# DB10011_Converter.net
KiCad netlist of a schematic drawn in Altium Designer
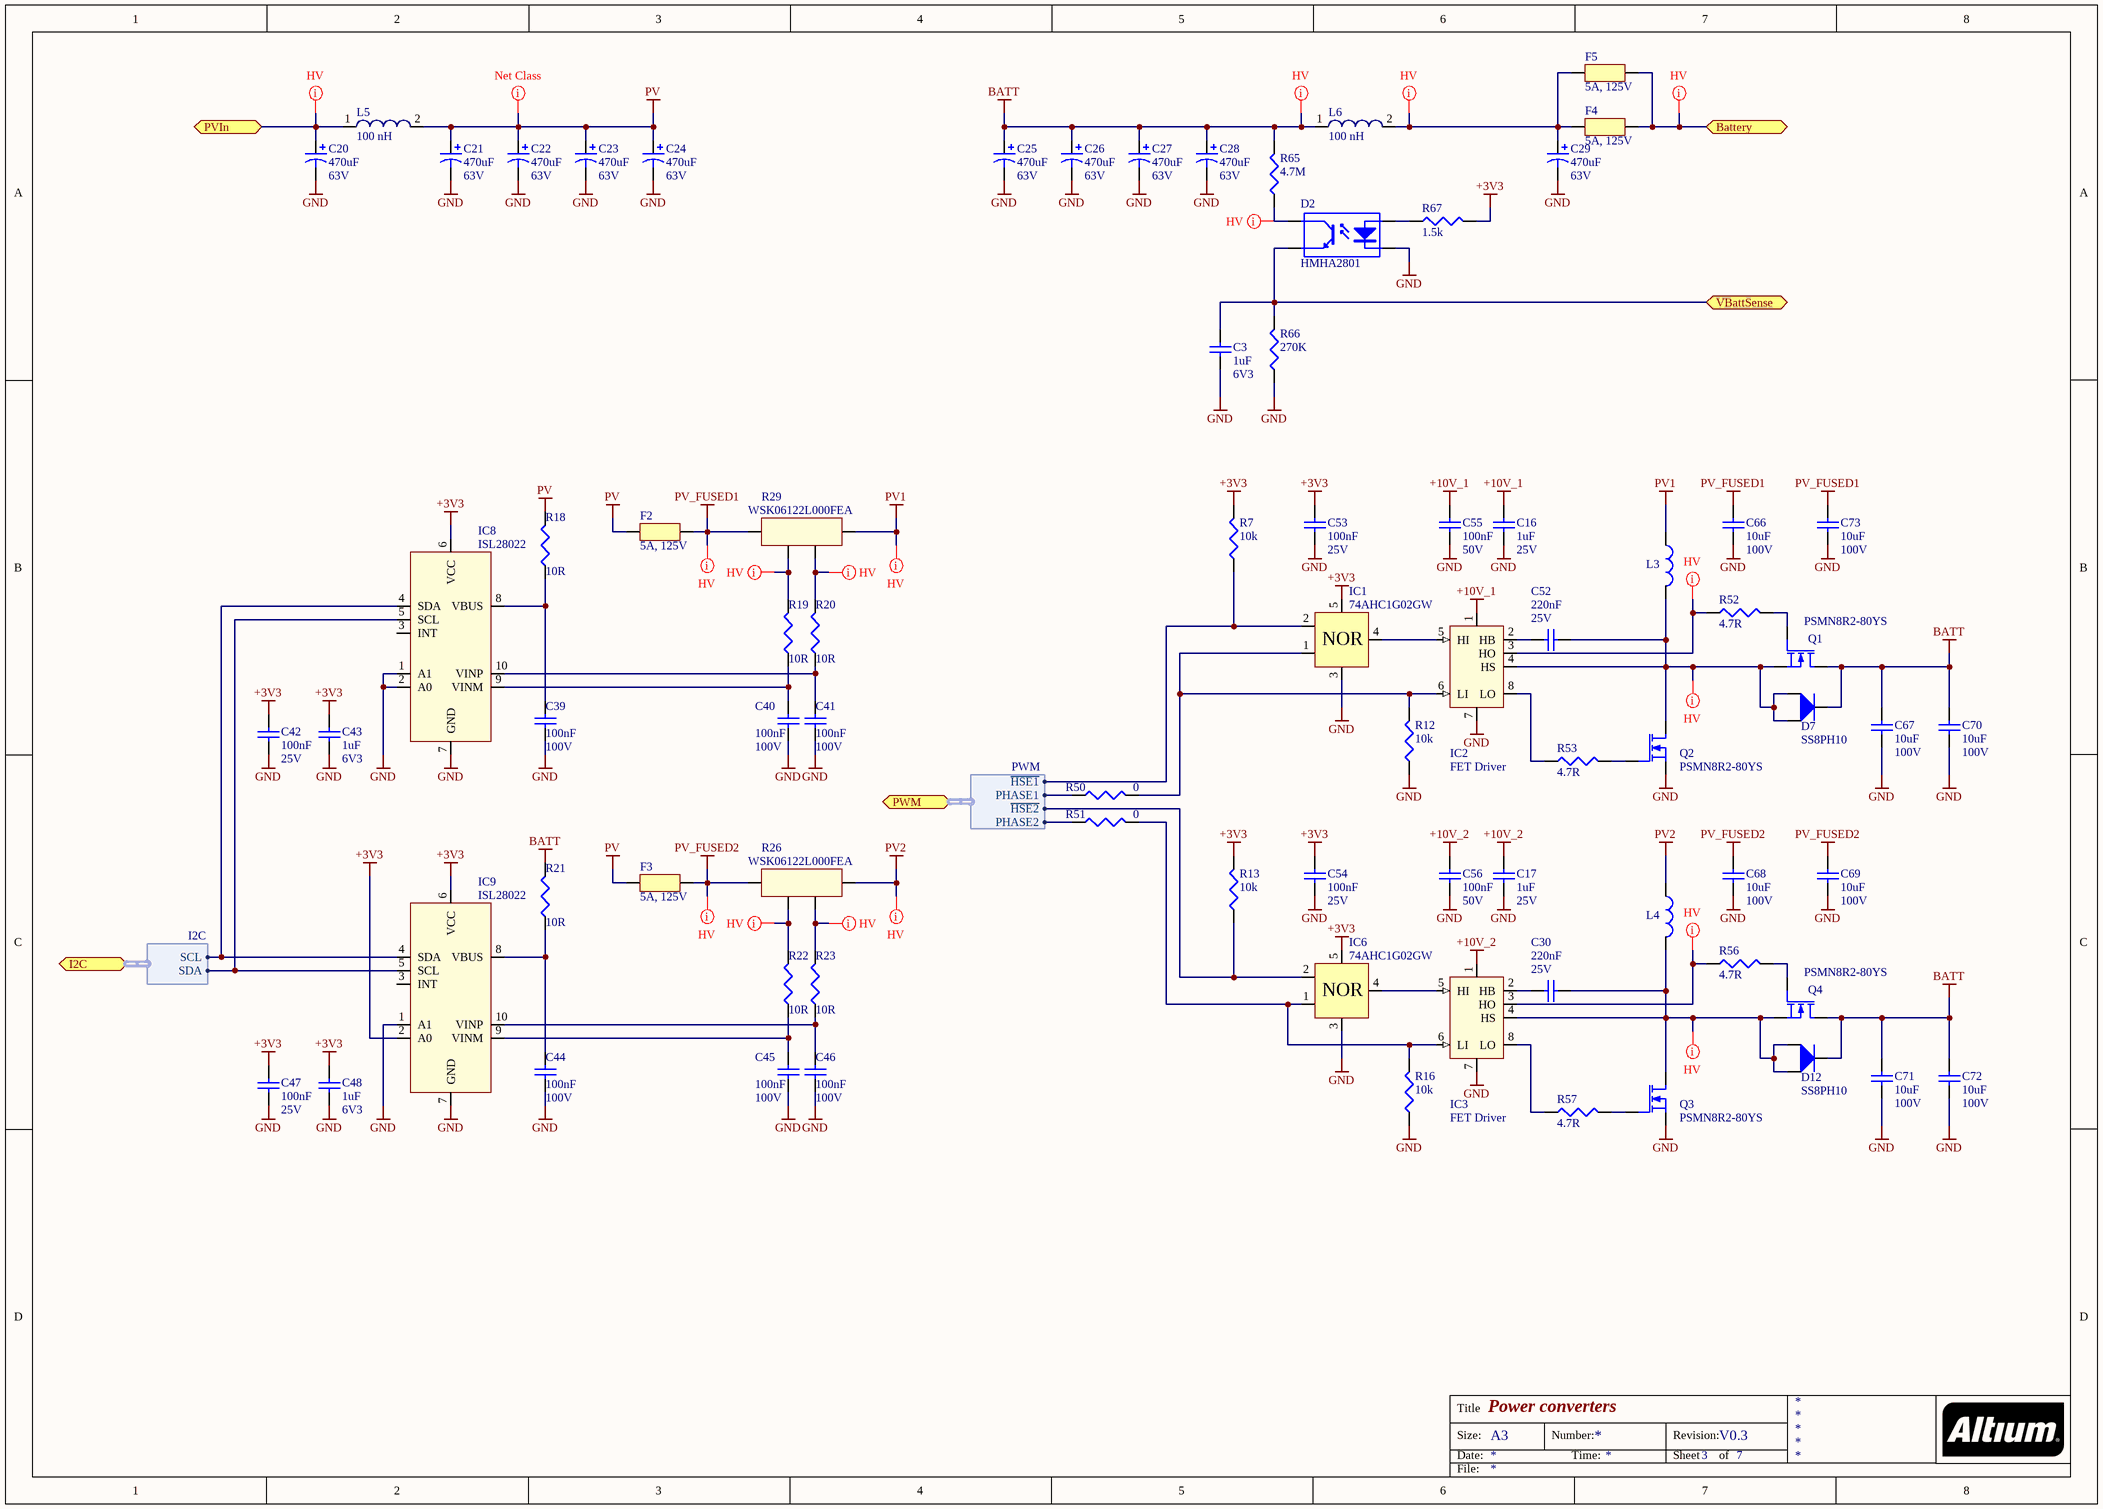
[diagram p0: DB10011_Converter.SchDoc]

(export (version "E")
  (design (tool "Eeschema 10.0.6"))
  (components
    (comp (ref "C3")
      (value "1uF")
      (footprint "C0402")
      (description "Capacitor, 1uF, 6.3V, X5R")
      (fields (field (name "VOLTAGE RATING") "6V3"))
      (libsource (lib "AR_Capacitors_Ceramic") (part "1uF/0402/CER/6.3V"))
    )
    (comp (ref "C16")
      (value "1uF")
      (footprint "C0603")
      (description "Capacitor, 1uF, 25V, X7R")
      (fields (field (name "VOLTAGE RATING") "25V"))
      (libsource (lib "AR_Capacitors_Ceramic") (part "1uF/0603/CER/25V"))
    )
    (comp (ref "C17")
      (value "1uF")
      (footprint "C0603")
      (description "Capacitor, 1uF, 25V, X7R")
      (fields (field (name "VOLTAGE RATING") "25V"))
      (libsource (lib "AR_Capacitors_Ceramic") (part "1uF/0603/CER/25V"))
    )
    (comp (ref "C20")
      (value "470uF")
      (footprint "Radial-16")
      (description "Aluminum Electrolytic Capacitor, 470uF, 63V")
      (fields (field (name "VOLTAGE RATING") "63V"))
      (libsource (lib "AR_Capacitors_Aluminium") (part "470uF/ALU/63V"))
    )
    (comp (ref "C21")
      (value "470uF")
      (footprint "Radial-16")
      (description "Aluminum Electrolytic Capacitor, 470uF, 63V")
      (fields (field (name "VOLTAGE RATING") "63V"))
      (libsource (lib "AR_Capacitors_Aluminium") (part "470uF/ALU/63V"))
    )
    (comp (ref "C22")
      (value "470uF")
      (footprint "Radial-16")
      (description "Aluminum Electrolytic Capacitor, 470uF, 63V")
      (fields (field (name "VOLTAGE RATING") "63V"))
      (libsource (lib "AR_Capacitors_Aluminium") (part "470uF/ALU/63V"))
    )
    (comp (ref "C23")
      (value "470uF")
      (footprint "Radial-16")
      (description "Aluminum Electrolytic Capacitor, 470uF, 63V")
      (fields (field (name "VOLTAGE RATING") "63V"))
      (libsource (lib "AR_Capacitors_Aluminium") (part "470uF/ALU/63V"))
    )
    (comp (ref "C24")
      (value "470uF")
      (footprint "Radial-16")
      (description "Aluminum Electrolytic Capacitor, 470uF, 63V")
      (fields (field (name "VOLTAGE RATING") "63V"))
      (libsource (lib "AR_Capacitors_Aluminium") (part "470uF/ALU/63V"))
    )
    (comp (ref "C25")
      (value "470uF")
      (footprint "Radial-16")
      (description "Aluminum Electrolytic Capacitor, 470uF, 63V")
      (fields (field (name "VOLTAGE RATING") "63V"))
      (libsource (lib "AR_Capacitors_Aluminium") (part "470uF/ALU/63V"))
    )
    (comp (ref "C26")
      (value "470uF")
      (footprint "Radial-16")
      (description "Aluminum Electrolytic Capacitor, 470uF, 63V")
      (fields (field (name "VOLTAGE RATING") "63V"))
      (libsource (lib "AR_Capacitors_Aluminium") (part "470uF/ALU/63V"))
    )
    (comp (ref "C27")
      (value "470uF")
      (footprint "Radial-16")
      (description "Aluminum Electrolytic Capacitor, 470uF, 63V")
      (fields (field (name "VOLTAGE RATING") "63V"))
      (libsource (lib "AR_Capacitors_Aluminium") (part "470uF/ALU/63V"))
    )
    (comp (ref "C28")
      (value "470uF")
      (footprint "Radial-16")
      (description "Aluminum Electrolytic Capacitor, 470uF, 63V")
      (fields (field (name "VOLTAGE RATING") "63V"))
      (libsource (lib "AR_Capacitors_Aluminium") (part "470uF/ALU/63V"))
    )
    (comp (ref "C29")
      (value "470uF")
      (footprint "Radial-16")
      (description "Aluminum Electrolytic Capacitor, 470uF, 63V")
      (fields (field (name "VOLTAGE RATING") "63V"))
      (libsource (lib "AR_Capacitors_Aluminium") (part "470uF/ALU/63V"))
    )
    (comp (ref "C30")
      (value "220nF")
      (footprint "C0603")
      (description "Capacitor, 220nF, 25V, X7R")
      (fields (field (name "VOLTAGE RATING") "25V"))
      (libsource (lib "AR_Capacitors_Ceramic") (part "220nF/0603/CER/25V"))
    )
    (comp (ref "C39")
      (value "100nF")
      (footprint "C-0805")
      (description "Capacitor, 100nF, 100V, X7R")
      (fields (field (name "VOLTAGE RATING") "100V"))
      (libsource (lib "AR_Capacitors_Ceramic") (part "100nF/0805/CER/100V"))
    )
    (comp (ref "C40")
      (value "100nF")
      (footprint "C-0805")
      (description "Capacitor, 100nF, 100V, X7R")
      (fields (field (name "VOLTAGE RATING") "100V"))
      (libsource (lib "AR_Capacitors_Ceramic") (part "100nF/0805/CER/100V"))
    )
    (comp (ref "C41")
      (value "100nF")
      (footprint "C-0805")
      (description "Capacitor, 100nF, 100V, X7R")
      (fields (field (name "VOLTAGE RATING") "100V"))
      (libsource (lib "AR_Capacitors_Ceramic") (part "100nF/0805/CER/100V"))
    )
    (comp (ref "C42")
      (value "100nF")
      (footprint "C0402")
      (description "Capacitor, 100nF, 25V, X7R")
      (fields (field (name "VOLTAGE RATING") "25V"))
      (libsource (lib "AR_Capacitors_Ceramic") (part "100nF/0402/CER/25V"))
    )
    (comp (ref "C43")
      (value "1uF")
      (footprint "C0402")
      (description "Capacitor, 1uF, 6.3V, X5R")
      (fields (field (name "VOLTAGE RATING") "6V3"))
      (libsource (lib "AR_Capacitors_Ceramic") (part "1uF/0402/CER/6.3V"))
    )
    (comp (ref "C44")
      (value "100nF")
      (footprint "C-0805")
      (description "Capacitor, 100nF, 100V, X7R")
      (fields (field (name "VOLTAGE RATING") "100V"))
      (libsource (lib "AR_Capacitors_Ceramic") (part "100nF/0805/CER/100V"))
    )
    (comp (ref "C45")
      (value "100nF")
      (footprint "C-0805")
      (description "Capacitor, 100nF, 100V, X7R")
      (fields (field (name "VOLTAGE RATING") "100V"))
      (libsource (lib "AR_Capacitors_Ceramic") (part "100nF/0805/CER/100V"))
    )
    (comp (ref "C46")
      (value "100nF")
      (footprint "C-0805")
      (description "Capacitor, 100nF, 100V, X7R")
      (fields (field (name "VOLTAGE RATING") "100V"))
      (libsource (lib "AR_Capacitors_Ceramic") (part "100nF/0805/CER/100V"))
    )
    (comp (ref "C47")
      (value "100nF")
      (footprint "C0402")
      (description "Capacitor, 100nF, 25V, X7R")
      (fields (field (name "VOLTAGE RATING") "25V"))
      (libsource (lib "AR_Capacitors_Ceramic") (part "100nF/0402/CER/25V"))
    )
    (comp (ref "C48")
      (value "1uF")
      (footprint "C0402")
      (description "Capacitor, 1uF, 6.3V, X5R")
      (fields (field (name "VOLTAGE RATING") "6V3"))
      (libsource (lib "AR_Capacitors_Ceramic") (part "1uF/0402/CER/6.3V"))
    )
    (comp (ref "C52")
      (value "220nF")
      (footprint "C0603")
      (description "Capacitor, 220nF, 25V, X7R")
      (fields (field (name "VOLTAGE RATING") "25V"))
      (libsource (lib "AR_Capacitors_Ceramic") (part "220nF/0603/CER/25V"))
    )
    (comp (ref "C53")
      (value "100nF")
      (footprint "C0402")
      (description "Capacitor, 100nF, 25V, X7R")
      (fields (field (name "VOLTAGE RATING") "25V"))
      (libsource (lib "AR_Capacitors_Ceramic") (part "100nF/0402/CER/25V"))
    )
    (comp (ref "C54")
      (value "100nF")
      (footprint "C0402")
      (description "Capacitor, 100nF, 25V, X7R")
      (fields (field (name "VOLTAGE RATING") "25V"))
      (libsource (lib "AR_Capacitors_Ceramic") (part "100nF/0402/CER/25V"))
    )
    (comp (ref "C55")
      (value "100nF")
      (footprint "C0603")
      (description "Capacitor, 100nF, 50V, X7R")
      (fields (field (name "VOLTAGE RATING") "50V"))
      (libsource (lib "AR_Capacitors_Ceramic") (part "100nF/0603/CER/50V"))
    )
    (comp (ref "C56")
      (value "100nF")
      (footprint "C0603")
      (description "Capacitor, 100nF, 50V, X7R")
      (fields (field (name "VOLTAGE RATING") "50V"))
      (libsource (lib "AR_Capacitors_Ceramic") (part "100nF/0603/CER/50V"))
    )
    (comp (ref "C66")
      (value "10uF")
      (footprint "C2220")
      (description "Capacitor, 10uF, 100V, X7S")
      (fields (field (name "VOLTAGE RATING") "100V"))
      (libsource (lib "AR_Capacitors_Ceramic") (part "10uF/2220/CER/100V"))
    )
    (comp (ref "C67")
      (value "10uF")
      (footprint "C2220")
      (description "Capacitor, 10uF, 100V, X7S")
      (fields (field (name "VOLTAGE RATING") "100V"))
      (libsource (lib "AR_Capacitors_Ceramic") (part "10uF/2220/CER/100V"))
    )
    (comp (ref "C68")
      (value "10uF")
      (footprint "C2220")
      (description "Capacitor, 10uF, 100V, X7S")
      (fields (field (name "VOLTAGE RATING") "100V"))
      (libsource (lib "AR_Capacitors_Ceramic") (part "10uF/2220/CER/100V"))
    )
    (comp (ref "C69")
      (value "10uF")
      (footprint "C2220")
      (description "Capacitor, 10uF, 100V, X7S")
      (fields (field (name "VOLTAGE RATING") "100V"))
      (libsource (lib "AR_Capacitors_Ceramic") (part "10uF/2220/CER/100V"))
    )
    (comp (ref "C70")
      (value "10uF")
      (footprint "C2220")
      (description "Capacitor, 10uF, 100V, X7S")
      (fields (field (name "VOLTAGE RATING") "100V"))
      (libsource (lib "AR_Capacitors_Ceramic") (part "10uF/2220/CER/100V"))
    )
    (comp (ref "C71")
      (value "10uF")
      (footprint "C2220")
      (description "Capacitor, 10uF, 100V, X7S")
      (fields (field (name "VOLTAGE RATING") "100V"))
      (libsource (lib "AR_Capacitors_Ceramic") (part "10uF/2220/CER/100V"))
    )
    (comp (ref "C72")
      (value "10uF")
      (footprint "C2220")
      (description "Capacitor, 10uF, 100V, X7S")
      (fields (field (name "VOLTAGE RATING") "100V"))
      (libsource (lib "AR_Capacitors_Ceramic") (part "10uF/2220/CER/100V"))
    )
    (comp (ref "C73")
      (value "10uF")
      (footprint "C2220")
      (description "Capacitor, 10uF, 100V, X7S")
      (fields (field (name "VOLTAGE RATING") "100V"))
      (libsource (lib "AR_Capacitors_Ceramic") (part "10uF/2220/CER/100V"))
    )
    (comp (ref "D2")
      (value "HMHA2801")
      (footprint "FSOP4")
      (description "Optocoupler, Vout:80V, Iin:0.01A")
      (libsource (lib "AR_Optocouplers") (part "HMHA2801"))
    )
    (comp (ref "D7")
      (value "SS8PH10")
      (footprint "TO277A")
      (description "Diode 8A 100V")
      (libsource (lib "DannyLib") (part "SS8PH10"))
    )
    (comp (ref "D12")
      (value "SS8PH10")
      (footprint "TO277A")
      (description "Diode 8A 100V")
      (libsource (lib "DannyLib") (part "SS8PH10"))
    )
    (comp (ref "F2")
      (value "5A, 125V")
      (footprint "SMF")
      (description "Fuse, Slow Blow, 5A, 125V, T:-55°C +125°C")
      (libsource (lib "AR_Misc") (part "0452005.MRL"))
    )
    (comp (ref "F3")
      (value "5A, 125V")
      (footprint "SMF")
      (description "Fuse, Slow Blow, 5A, 125V, T:-55°C +125°C")
      (libsource (lib "AR_Misc") (part "0452005.MRL"))
    )
    (comp (ref "F4")
      (value "5A, 125V")
      (footprint "SMF")
      (description "Fuse, Slow Blow, 5A, 125V, T:-55°C +125°C")
      (libsource (lib "AR_Misc") (part "0452005.MRL"))
    )
    (comp (ref "F5")
      (value "5A, 125V")
      (footprint "SMF")
      (description "Fuse, Slow Blow, 5A, 125V, T:-55°C +125°C")
      (libsource (lib "AR_Misc") (part "0452005.MRL"))
    )
    (comp (ref "IC1")
      (value "74AHC1G02GW")
      (footprint "SOT-23-5")
      (description "LOGIC, NOR Gate 2-Input")
      (libsource (lib "AR_ICs") (part "74AHC1G02GW"))
    )
    (comp (ref "IC2")
      (value "FET Driver")
      (footprint "SO-8")
      (description "Half bridge FET driver")
      (libsource (lib "AR_ICs") (part "UCC27211"))
    )
    (comp (ref "IC3")
      (value "FET Driver")
      (footprint "SO-8")
      (description "Half bridge FET driver")
      (libsource (lib "AR_ICs") (part "UCC27211"))
    )
    (comp (ref "IC6")
      (value "74AHC1G02GW")
      (footprint "SOT-23-5")
      (description "LOGIC, NOR Gate 2-Input")
      (libsource (lib "AR_ICs") (part "74AHC1G02GW"))
    )
    (comp (ref "IC8")
      (value "ISL28022")
      (footprint "MSOP10")
      (description "Current and voltage ADC")
      (libsource (lib "AR_ICs") (part "ISL28022"))
    )
    (comp (ref "IC9")
      (value "ISL28022")
      (footprint "MSOP10")
      (description "Current and voltage ADC")
      (libsource (lib "AR_ICs") (part "ISL28022"))
    )
    (comp (ref "L3")
      (value "ETD39Custom")
      (footprint "ETD39")
      (description "Custom inductor for MPPT")
      (fields (field (name "MANUFACTURER") "FERROXCUBE"))
      (libsource (lib "AR_Inductors") (part "ETD39Custom"))
    )
    (comp (ref "L4")
      (value "ETD39Custom")
      (footprint "ETD39")
      (description "Custom inductor for MPPT")
      (fields (field (name "MANUFACTURER") "FERROXCUBE"))
      (libsource (lib "AR_Inductors") (part "ETD39Custom"))
    )
    (comp (ref "L5")
      (value "100 nH")
      (footprint "WE-HCM 1240")
      (description "SMD Flat Wire Inductor WE-HCM Hight Current, L=100 nH")
      (fields (field (name "PARTNO") "744304010") (field (name "CREATED BY") "Christin Zierenner"))
      (libsource (lib "Altium_WE_eiSos_2-3_High_Current_Choke") (part "WE-HCM 1240, 744304010"))
    )
    (comp (ref "L6")
      (value "100 nH")
      (footprint "WE-HCM 1240")
      (description "SMD Flat Wire Inductor WE-HCM Hight Current, L=100 nH")
      (fields (field (name "PARTNO") "744304010") (field (name "CREATED BY") "Christin Zierenner"))
      (libsource (lib "Altium_WE_eiSos_2-3_High_Current_Choke") (part "WE-HCM 1240, 744304010"))
    )
    (comp (ref "Q1")
      (value "PSMN8R2-80YS")
      (footprint "SOT-669")
      (description "Mosfet, N-channel, Vds:80V, Id:82A, Vgs-th:4V, Rds-on:0.0058ohm")
      (libsource (lib "AR_Mosfets") (part "PSMN8R2-80YS"))
    )
    (comp (ref "Q2")
      (value "PSMN8R2-80YS")
      (footprint "SOT-669")
      (description "Mosfet, N-channel, Vds:80V, Id:82A, Vgs-th:4V, Rds-on:0.0058ohm")
      (libsource (lib "AR_Mosfets") (part "PSMN8R2-80YS"))
    )
    (comp (ref "Q3")
      (value "PSMN8R2-80YS")
      (footprint "SOT-669")
      (description "Mosfet, N-channel, Vds:80V, Id:82A, Vgs-th:4V, Rds-on:0.0058ohm")
      (libsource (lib "AR_Mosfets") (part "PSMN8R2-80YS"))
    )
    (comp (ref "Q4")
      (value "PSMN8R2-80YS")
      (footprint "SOT-669")
      (description "Mosfet, N-channel, Vds:80V, Id:82A, Vgs-th:4V, Rds-on:0.0058ohm")
      (libsource (lib "AR_Mosfets") (part "PSMN8R2-80YS"))
    )
    (comp (ref "R7")
      (value "10k")
      (footprint "0402")
      (description "Resistor, 10k, 0.1%, 0.0625W, 50V, 100PPM, 0402")
      (libsource (lib "AR_Resistors_SMD") (part "10k/0402/0063W/50V"))
    )
    (comp (ref "R12")
      (value "10k")
      (footprint "0402")
      (description "Resistor, 10k, 0.1%, 0.0625W, 50V, 100PPM, 0402")
      (libsource (lib "AR_Resistors_SMD") (part "10k/0402/0063W/50V"))
    )
    (comp (ref "R13")
      (value "10k")
      (footprint "0402")
      (description "Resistor, 10k, 0.1%, 0.0625W, 50V, 100PPM, 0402")
      (libsource (lib "AR_Resistors_SMD") (part "10k/0402/0063W/50V"))
    )
    (comp (ref "R16")
      (value "10k")
      (footprint "0402")
      (description "Resistor, 10k, 0.1%, 0.0625W, 50V, 100PPM, 0402")
      (libsource (lib "AR_Resistors_SMD") (part "10k/0402/0063W/50V"))
    )
    (comp (ref "R18")
      (value "10R")
      (footprint "0603")
      (description "Resistor, 10R, 1%, 0.063W, 50V, 200PPM, 0603")
      (libsource (lib "AR_Resistors_SMD") (part "10/0603/0063W/50V"))
    )
    (comp (ref "R19")
      (value "10R")
      (footprint "0603")
      (description "Resistor, 10R, 1%, 0.063W, 50V, 200PPM, 0603")
      (libsource (lib "AR_Resistors_SMD") (part "10/0603/0063W/50V"))
    )
    (comp (ref "R20")
      (value "10R")
      (footprint "0603")
      (description "Resistor, 10R, 1%, 0.063W, 50V, 200PPM, 0603")
      (libsource (lib "AR_Resistors_SMD") (part "10/0603/0063W/50V"))
    )
    (comp (ref "R21")
      (value "10R")
      (footprint "0603")
      (description "Resistor, 10R, 1%, 0.063W, 50V, 200PPM, 0603")
      (libsource (lib "AR_Resistors_SMD") (part "10/0603/0063W/50V"))
    )
    (comp (ref "R22")
      (value "10R")
      (footprint "0603")
      (description "Resistor, 10R, 1%, 0.063W, 50V, 200PPM, 0603")
      (libsource (lib "AR_Resistors_SMD") (part "10/0603/0063W/50V"))
    )
    (comp (ref "R23")
      (value "10R")
      (footprint "0603")
      (description "Resistor, 10R, 1%, 0.063W, 50V, 200PPM, 0603")
      (libsource (lib "AR_Resistors_SMD") (part "10/0603/0063W/50V"))
    )
    (comp (ref "R26")
      (value "WSK06122L000FEA")
      (footprint "WSK0612")
      (description "RES, METAL STRIP, 0.002OHM, 1%")
      (libsource (lib "DannyLib") (part "WSK06122L000FEA"))
    )
    (comp (ref "R29")
      (value "WSK06122L000FEA")
      (footprint "WSK0612")
      (description "RES, METAL STRIP, 0.002OHM, 1%")
      (libsource (lib "DannyLib") (part "WSK06122L000FEA"))
    )
    (comp (ref "R50")
      (value "0")
      (footprint "0402")
      (description "Resistor, 0, 0.1%, 0.0625W, 50V, 100PPM, 0402")
      (libsource (lib "AR_Resistors_SMD") (part "0/0402/0063W/50V"))
    )
    (comp (ref "R51")
      (value "0")
      (footprint "0402")
      (description "Resistor, 0, 0.1%, 0.0625W, 50V, 100PPM, 0402")
      (libsource (lib "AR_Resistors_SMD") (part "0/0402/0063W/50V"))
    )
    (comp (ref "R52")
      (value "4.7R")
      (footprint "0603")
      (description "Resistor, 4.7R, 1%, 0.063W, 50V, 200PPM, 0603")
      (libsource (lib "AR_Resistors_SMD") (part "4.7/0603/0063W/50V"))
    )
    (comp (ref "R53")
      (value "4.7R")
      (footprint "0603")
      (description "Resistor, 4.7R, 1%, 0.063W, 50V, 200PPM, 0603")
      (libsource (lib "AR_Resistors_SMD") (part "4.7/0603/0063W/50V"))
    )
    (comp (ref "R56")
      (value "4.7R")
      (footprint "0603")
      (description "Resistor, 4.7R, 1%, 0.063W, 50V, 200PPM, 0603")
      (libsource (lib "AR_Resistors_SMD") (part "4.7/0603/0063W/50V"))
    )
    (comp (ref "R57")
      (value "4.7R")
      (footprint "0603")
      (description "Resistor, 4.7R, 1%, 0.063W, 50V, 200PPM, 0603")
      (libsource (lib "AR_Resistors_SMD") (part "4.7/0603/0063W/50V"))
    )
    (comp (ref "R65")
      (value "4.7M")
      (footprint "0805")
      (description "Resistor, 4.7M, 1%, 0.25W, 150V, 100PPM, 0805")
      (libsource (lib "AR_Resistors_SMD") (part "4.7M/0805/0250W/150V"))
    )
    (comp (ref "R66")
      (value "270K")
      (footprint "0402")
      (description "Resistor, 270k, 0.1%, 0.0625W, 50V, 100PPM, 0402")
      (libsource (lib "AR_Resistors_SMD") (part "270k/0402/0063W/50V"))
    )
    (comp (ref "R67")
      (value "1.5k")
      (footprint "0402")
      (description "Resistor, 1.5k, 0.1%, 0.0625W, 50V, 100PPM, 0402")
      (libsource (lib "AR_Resistors_SMD") (part "1.5k/0402/0063W/50V"))
    )
  )
  (nets
    (net (code "3") (name "+3V3") (class "Default")
      (node (ref "C42") (pin "2") (pinfunction "2_2") (pintype "passive"))
      (node (ref "C43") (pin "2") (pinfunction "2_2") (pintype "passive"))
      (node (ref "C47") (pin "2") (pinfunction "2_2") (pintype "passive"))
      (node (ref "C48") (pin "2") (pinfunction "2_2") (pintype "passive"))
      (node (ref "C53") (pin "1") (pinfunction "1_1") (pintype "passive"))
      (node (ref "C54") (pin "1") (pinfunction "1_1") (pintype "passive"))
      (node (ref "IC1") (pin "5") (pinfunction "VCC_5") (pintype "power_in"))
      (node (ref "IC6") (pin "5") (pinfunction "VCC_5") (pintype "power_in"))
      (node (ref "IC8") (pin "6") (pinfunction "VCC_6") (pintype "power_in"))
      (node (ref "IC9") (pin "2") (pinfunction "A0_2") (pintype "power_in"))
      (node (ref "IC9") (pin "6") (pinfunction "VCC_6") (pintype "power_in"))
      (node (ref "R13") (pin "2") (pinfunction "2_2") (pintype "passive"))
      (node (ref "R67") (pin "2") (pinfunction "2_2") (pintype "passive"))
      (node (ref "R7") (pin "2") (pinfunction "2_2") (pintype "passive"))
    )
    (net (code "4") (name "+10V_1") (class "Default")
      (node (ref "C16") (pin "2") (pinfunction "2_2") (pintype "passive"))
      (node (ref "C55") (pin "1") (pinfunction "1_1") (pintype "passive"))
      (node (ref "IC2") (pin "1") (pinfunction "VDD_1") (pintype "power_in"))
    )
    (net (code "5") (name "+10V_2") (class "Default")
      (node (ref "C17") (pin "2") (pinfunction "2_2") (pintype "passive"))
      (node (ref "C56") (pin "1") (pinfunction "1_1") (pintype "passive"))
      (node (ref "IC3") (pin "1") (pinfunction "VDD_1") (pintype "power_in"))
    )
    (net (code "6") (name "/Battery") (class "Default")
      (node (ref "F4") (pin "2") (pinfunction "2_2") (pintype "passive"))
      (node (ref "F5") (pin "2") (pinfunction "2_2") (pintype "passive"))
    )
    (net (code "7") (name "/PHASE1") (class "Default")
      (node (ref "R50") (pin "1") (pinfunction "1_1") (pintype "passive"))
    )
    (net (code "8") (name "/PHASE2") (class "Default")
      (node (ref "R51") (pin "1") (pinfunction "1_1") (pintype "passive"))
    )
    (net (code "9") (name "/PVIn") (class "Default")
      (node (ref "C20") (pin "1") (pinfunction "1_1") (pintype "passive"))
      (node (ref "L5") (pin "1") (pinfunction "1_1") (pintype "passive"))
    )
    (net (code "10") (name "/SCL") (class "Default")
      (node (ref "IC8") (pin "4") (pinfunction "SDA_4") (pintype "power_in"))
      (node (ref "IC9") (pin "4") (pinfunction "SDA_4") (pintype "power_in"))
    )
    (net (code "11") (name "/SDA") (class "Default")
      (node (ref "IC8") (pin "5") (pinfunction "SCL_5") (pintype "power_in"))
      (node (ref "IC9") (pin "5") (pinfunction "SCL_5") (pintype "power_in"))
    )
    (net (code "12") (name "/VBattSense") (class "Default")
      (node (ref "C3") (pin "2") (pinfunction "2_2") (pintype "passive"))
      (node (ref "D2") (pin "3") (pinfunction "E1_3") (pintype "passive"))
      (node (ref "R66") (pin "2") (pinfunction "2_2") (pintype "passive"))
    )
    (net (code "15") (name "/~{HSE1}") (class "Default")
      (node (ref "IC1") (pin "2") (pinfunction "A_2") (pintype "power_in"))
      (node (ref "R7") (pin "1") (pinfunction "1_1") (pintype "passive"))
    )
    (net (code "16") (name "/~{HSE2}") (class "Default")
      (node (ref "IC6") (pin "2") (pinfunction "A_2") (pintype "power_in"))
      (node (ref "R13") (pin "1") (pinfunction "1_1") (pintype "passive"))
    )
    (net (code "17") (name "BATT") (class "Default")
      (node (ref "C25") (pin "1") (pinfunction "1_1") (pintype "passive"))
      (node (ref "C26") (pin "1") (pinfunction "1_1") (pintype "passive"))
      (node (ref "C27") (pin "1") (pinfunction "1_1") (pintype "passive"))
      (node (ref "C28") (pin "1") (pinfunction "1_1") (pintype "passive"))
      (node (ref "C67") (pin "2") (pinfunction "2_2") (pintype "passive"))
      (node (ref "C70") (pin "2") (pinfunction "2_2") (pintype "passive"))
      (node (ref "C71") (pin "2") (pinfunction "2_2") (pintype "passive"))
      (node (ref "C72") (pin "2") (pinfunction "2_2") (pintype "passive"))
      (node (ref "D12") (pin "K") (pinfunction "K_K") (pintype "passive"))
      (node (ref "D7") (pin "K") (pinfunction "K_K") (pintype "passive"))
      (node (ref "L6") (pin "1") (pinfunction "1_1") (pintype "passive"))
      (node (ref "Q1") (pin "D") (pinfunction "D_D") (pintype "passive"))
      (node (ref "Q4") (pin "D") (pinfunction "D_D") (pintype "passive"))
      (node (ref "R21") (pin "2") (pinfunction "2_2") (pintype "passive"))
      (node (ref "R65") (pin "2") (pinfunction "2_2") (pintype "passive"))
    )
    (net (code "18") (name "GND") (class "Default")
      (node (ref "C16") (pin "1") (pinfunction "1_1") (pintype "passive"))
      (node (ref "C17") (pin "1") (pinfunction "1_1") (pintype "passive"))
      (node (ref "C20") (pin "2") (pinfunction "2_2") (pintype "passive"))
      (node (ref "C21") (pin "2") (pinfunction "2_2") (pintype "passive"))
      (node (ref "C22") (pin "2") (pinfunction "2_2") (pintype "passive"))
      (node (ref "C23") (pin "2") (pinfunction "2_2") (pintype "passive"))
      (node (ref "C24") (pin "2") (pinfunction "2_2") (pintype "passive"))
      (node (ref "C25") (pin "2") (pinfunction "2_2") (pintype "passive"))
      (node (ref "C26") (pin "2") (pinfunction "2_2") (pintype "passive"))
      (node (ref "C27") (pin "2") (pinfunction "2_2") (pintype "passive"))
      (node (ref "C28") (pin "2") (pinfunction "2_2") (pintype "passive"))
      (node (ref "C29") (pin "2") (pinfunction "2_2") (pintype "passive"))
      (node (ref "C3") (pin "1") (pinfunction "1_1") (pintype "passive"))
      (node (ref "C39") (pin "1") (pinfunction "1_1") (pintype "passive"))
      (node (ref "C40") (pin "1") (pinfunction "1_1") (pintype "passive"))
      (node (ref "C41") (pin "1") (pinfunction "1_1") (pintype "passive"))
      (node (ref "C42") (pin "1") (pinfunction "1_1") (pintype "passive"))
      (node (ref "C43") (pin "1") (pinfunction "1_1") (pintype "passive"))
      (node (ref "C44") (pin "1") (pinfunction "1_1") (pintype "passive"))
      (node (ref "C45") (pin "1") (pinfunction "1_1") (pintype "passive"))
      (node (ref "C46") (pin "1") (pinfunction "1_1") (pintype "passive"))
      (node (ref "C47") (pin "1") (pinfunction "1_1") (pintype "passive"))
      (node (ref "C48") (pin "1") (pinfunction "1_1") (pintype "passive"))
      (node (ref "C53") (pin "2") (pinfunction "2_2") (pintype "passive"))
      (node (ref "C54") (pin "2") (pinfunction "2_2") (pintype "passive"))
      (node (ref "C55") (pin "2") (pinfunction "2_2") (pintype "passive"))
      (node (ref "C56") (pin "2") (pinfunction "2_2") (pintype "passive"))
      (node (ref "C66") (pin "1") (pinfunction "1_1") (pintype "passive"))
      (node (ref "C67") (pin "1") (pinfunction "1_1") (pintype "passive"))
      (node (ref "C68") (pin "1") (pinfunction "1_1") (pintype "passive"))
      (node (ref "C69") (pin "1") (pinfunction "1_1") (pintype "passive"))
      (node (ref "C70") (pin "1") (pinfunction "1_1") (pintype "passive"))
      (node (ref "C71") (pin "1") (pinfunction "1_1") (pintype "passive"))
      (node (ref "C72") (pin "1") (pinfunction "1_1") (pintype "passive"))
      (node (ref "C73") (pin "1") (pinfunction "1_1") (pintype "passive"))
      (node (ref "D2") (pin "2") (pinfunction "K1_2") (pintype "passive"))
      (node (ref "IC1") (pin "3") (pinfunction "GND_3") (pintype "power_in"))
      (node (ref "IC2") (pin "7") (pinfunction "VSS_7") (pintype "power_in"))
      (node (ref "IC3") (pin "7") (pinfunction "VSS_7") (pintype "power_in"))
      (node (ref "IC6") (pin "3") (pinfunction "GND_3") (pintype "power_in"))
      (node (ref "IC8") (pin "1") (pinfunction "A1_1") (pintype "power_in"))
      (node (ref "IC8") (pin "2") (pinfunction "A0_2") (pintype "power_in"))
      (node (ref "IC8") (pin "7") (pinfunction "GND_7") (pintype "power_in"))
      (node (ref "IC9") (pin "1") (pinfunction "A1_1") (pintype "power_in"))
      (node (ref "IC9") (pin "7") (pinfunction "GND_7") (pintype "power_in"))
      (node (ref "Q2") (pin "S") (pinfunction "S_S") (pintype "passive"))
      (node (ref "Q3") (pin "S") (pinfunction "S_S") (pintype "passive"))
      (node (ref "R12") (pin "1") (pinfunction "1_1") (pintype "passive"))
      (node (ref "R16") (pin "1") (pinfunction "1_1") (pintype "passive"))
      (node (ref "R66") (pin "1") (pinfunction "1_1") (pintype "passive"))
    )
    (net (code "19") (name "Net-(C29-Pad1)") (class "Default")
      (node (ref "C29") (pin "1") (pinfunction "1_1") (pintype "passive"))
      (node (ref "F4") (pin "1") (pinfunction "1_1") (pintype "passive"))
      (node (ref "F5") (pin "1") (pinfunction "1_1") (pintype "passive"))
      (node (ref "L6") (pin "2") (pinfunction "2_2") (pintype "passive"))
    )
    (net (code "20") (name "Net-(D2-A1)") (class "Default")
      (node (ref "D2") (pin "1") (pinfunction "A1_1") (pintype "passive"))
      (node (ref "R67") (pin "1") (pinfunction "1_1") (pintype "passive"))
    )
    (net (code "21") (name "Net-(D2-C1)") (class "Default")
      (node (ref "D2") (pin "4") (pinfunction "C1_4") (pintype "passive"))
      (node (ref "R65") (pin "1") (pinfunction "1_1") (pintype "passive"))
    )
    (net (code "22") (name "Net-(IC1-B)") (class "Default")
      (node (ref "IC1") (pin "1") (pinfunction "B_1") (pintype "power_in"))
      (node (ref "IC2") (pin "6") (pinfunction "LI_6") (pintype "input"))
      (node (ref "R12") (pin "2") (pinfunction "2_2") (pintype "passive"))
      (node (ref "R50") (pin "2") (pinfunction "2_2") (pintype "passive"))
    )
    (net (code "23") (name "Net-(IC1-Y)") (class "Default")
      (node (ref "IC1") (pin "4") (pinfunction "Y_4") (pintype "power_in"))
      (node (ref "IC2") (pin "5") (pinfunction "HI_5") (pintype "input"))
    )
    (net (code "24") (name "Net-(IC2-HB)") (class "Default")
      (node (ref "C52") (pin "2") (pinfunction "2_2") (pintype "passive"))
      (node (ref "IC2") (pin "2") (pinfunction "HB_2") (pintype "passive"))
    )
    (net (code "25") (name "Net-(IC2-HO)") (class "Default")
      (node (ref "IC2") (pin "3") (pinfunction "HO_3") (pintype "passive"))
      (node (ref "R52") (pin "1") (pinfunction "1_1") (pintype "passive"))
    )
    (net (code "26") (name "Net-(IC2-HS)") (class "Default")
      (node (ref "C52") (pin "1") (pinfunction "1_1") (pintype "passive"))
      (node (ref "D7") (pin "1") (pinfunction "A_1") (pintype "passive"))
      (node (ref "D7") (pin "2") (pinfunction "A_2") (pintype "passive"))
      (node (ref "IC2") (pin "4") (pinfunction "HS_4") (pintype "passive"))
      (node (ref "L3") (pin "2") (pinfunction "2_2") (pintype "passive"))
      (node (ref "Q1") (pin "S") (pinfunction "S_S") (pintype "passive"))
      (node (ref "Q2") (pin "D") (pinfunction "D_D") (pintype "passive"))
    )
    (net (code "27") (name "Net-(IC2-LO)") (class "Default")
      (node (ref "IC2") (pin "8") (pinfunction "LO_8") (pintype "passive"))
      (node (ref "R53") (pin "1") (pinfunction "1_1") (pintype "passive"))
    )
    (net (code "28") (name "Net-(IC3-HB)") (class "Default")
      (node (ref "C30") (pin "2") (pinfunction "2_2") (pintype "passive"))
      (node (ref "IC3") (pin "2") (pinfunction "HB_2") (pintype "passive"))
    )
    (net (code "29") (name "Net-(IC3-HI)") (class "Default")
      (node (ref "IC3") (pin "5") (pinfunction "HI_5") (pintype "input"))
      (node (ref "IC6") (pin "4") (pinfunction "Y_4") (pintype "power_in"))
    )
    (net (code "30") (name "Net-(IC3-HO)") (class "Default")
      (node (ref "IC3") (pin "3") (pinfunction "HO_3") (pintype "passive"))
      (node (ref "R56") (pin "1") (pinfunction "1_1") (pintype "passive"))
    )
    (net (code "31") (name "Net-(IC3-HS)") (class "Default")
      (node (ref "C30") (pin "1") (pinfunction "1_1") (pintype "passive"))
      (node (ref "D12") (pin "1") (pinfunction "A_1") (pintype "passive"))
      (node (ref "D12") (pin "2") (pinfunction "A_2") (pintype "passive"))
      (node (ref "IC3") (pin "4") (pinfunction "HS_4") (pintype "passive"))
      (node (ref "L4") (pin "2") (pinfunction "2_2") (pintype "passive"))
      (node (ref "Q3") (pin "D") (pinfunction "D_D") (pintype "passive"))
      (node (ref "Q4") (pin "S") (pinfunction "S_S") (pintype "passive"))
    )
    (net (code "32") (name "Net-(IC3-LI)") (class "Default")
      (node (ref "IC3") (pin "6") (pinfunction "LI_6") (pintype "input"))
      (node (ref "IC6") (pin "1") (pinfunction "B_1") (pintype "power_in"))
      (node (ref "R16") (pin "2") (pinfunction "2_2") (pintype "passive"))
      (node (ref "R51") (pin "2") (pinfunction "2_2") (pintype "passive"))
    )
    (net (code "33") (name "Net-(IC3-LO)") (class "Default")
      (node (ref "IC3") (pin "8") (pinfunction "LO_8") (pintype "passive"))
      (node (ref "R57") (pin "1") (pinfunction "1_1") (pintype "passive"))
    )
    (net (code "34") (name "Net-(IC8-VBUS)") (class "Default")
      (node (ref "C39") (pin "2") (pinfunction "2_2") (pintype "passive"))
      (node (ref "IC8") (pin "8") (pinfunction "VBUS_8") (pintype "power_in"))
      (node (ref "R18") (pin "1") (pinfunction "1_1") (pintype "passive"))
    )
    (net (code "35") (name "Net-(IC8-VINM)") (class "Default")
      (node (ref "C40") (pin "2") (pinfunction "2_2") (pintype "passive"))
      (node (ref "IC8") (pin "9") (pinfunction "VINM_9") (pintype "power_in"))
      (node (ref "R19") (pin "1") (pinfunction "1_1") (pintype "passive"))
    )
    (net (code "36") (name "Net-(IC8-VINP)") (class "Default")
      (node (ref "C41") (pin "2") (pinfunction "2_2") (pintype "passive"))
      (node (ref "IC8") (pin "10") (pinfunction "VINP_10") (pintype "power_in"))
      (node (ref "R20") (pin "1") (pinfunction "1_1") (pintype "passive"))
    )
    (net (code "37") (name "Net-(IC9-VBUS)") (class "Default")
      (node (ref "C44") (pin "2") (pinfunction "2_2") (pintype "passive"))
      (node (ref "IC9") (pin "8") (pinfunction "VBUS_8") (pintype "power_in"))
      (node (ref "R21") (pin "1") (pinfunction "1_1") (pintype "passive"))
    )
    (net (code "38") (name "Net-(IC9-VINM)") (class "Default")
      (node (ref "C45") (pin "2") (pinfunction "2_2") (pintype "passive"))
      (node (ref "IC9") (pin "9") (pinfunction "VINM_9") (pintype "power_in"))
      (node (ref "R22") (pin "1") (pinfunction "1_1") (pintype "passive"))
    )
    (net (code "39") (name "Net-(IC9-VINP)") (class "Default")
      (node (ref "C46") (pin "2") (pinfunction "2_2") (pintype "passive"))
      (node (ref "IC9") (pin "10") (pinfunction "VINP_10") (pintype "power_in"))
      (node (ref "R23") (pin "1") (pinfunction "1_1") (pintype "passive"))
    )
    (net (code "40") (name "Net-(Q1-PadG)") (class "Default")
      (node (ref "Q1") (pin "G") (pinfunction "G_G") (pintype "passive"))
      (node (ref "R52") (pin "2") (pinfunction "2_2") (pintype "passive"))
    )
    (net (code "41") (name "Net-(Q2-PadG)") (class "Default")
      (node (ref "Q2") (pin "G") (pinfunction "G_G") (pintype "passive"))
      (node (ref "R53") (pin "2") (pinfunction "2_2") (pintype "passive"))
    )
    (net (code "42") (name "Net-(Q3-PadG)") (class "Default")
      (node (ref "Q3") (pin "G") (pinfunction "G_G") (pintype "passive"))
      (node (ref "R57") (pin "2") (pinfunction "2_2") (pintype "passive"))
    )
    (net (code "43") (name "Net-(Q4-PadG)") (class "Default")
      (node (ref "Q4") (pin "G") (pinfunction "G_G") (pintype "passive"))
      (node (ref "R56") (pin "2") (pinfunction "2_2") (pintype "passive"))
    )
    (net (code "44") (name "Net-(R19-Pad2)") (class "Default")
      (node (ref "R19") (pin "2") (pinfunction "2_2") (pintype "passive"))
      (node (ref "R29") (pin "bs") (pinfunction "bs_bs") (pintype "passive"))
    )
    (net (code "45") (name "Net-(R20-Pad2)") (class "Default")
      (node (ref "R20") (pin "2") (pinfunction "2_2") (pintype "passive"))
      (node (ref "R29") (pin "as") (pinfunction "as_as") (pintype "passive"))
    )
    (net (code "46") (name "Net-(R22-Pad2)") (class "Default")
      (node (ref "R22") (pin "2") (pinfunction "2_2") (pintype "passive"))
      (node (ref "R26") (pin "bs") (pinfunction "bs_bs") (pintype "passive"))
    )
    (net (code "47") (name "Net-(R23-Pad2)") (class "Default")
      (node (ref "R23") (pin "2") (pinfunction "2_2") (pintype "passive"))
      (node (ref "R26") (pin "as") (pinfunction "as_as") (pintype "passive"))
    )
    (net (code "48") (name "PV") (class "Default")
      (node (ref "C21") (pin "1") (pinfunction "1_1") (pintype "passive"))
      (node (ref "C22") (pin "1") (pinfunction "1_1") (pintype "passive"))
      (node (ref "C23") (pin "1") (pinfunction "1_1") (pintype "passive"))
      (node (ref "C24") (pin "1") (pinfunction "1_1") (pintype "passive"))
      (node (ref "F2") (pin "1") (pinfunction "1_1") (pintype "passive"))
      (node (ref "F3") (pin "1") (pinfunction "1_1") (pintype "passive"))
      (node (ref "L5") (pin "2") (pinfunction "2_2") (pintype "passive"))
      (node (ref "R18") (pin "2") (pinfunction "2_2") (pintype "passive"))
    )
    (net (code "49") (name "PV1") (class "Default")
      (node (ref "L3") (pin "1") (pinfunction "1_1") (pintype "passive"))
      (node (ref "R29") (pin "a") (pinfunction "a_a") (pintype "passive"))
    )
    (net (code "50") (name "PV2") (class "Default")
      (node (ref "L4") (pin "1") (pinfunction "1_1") (pintype "passive"))
      (node (ref "R26") (pin "a") (pinfunction "a_a") (pintype "passive"))
    )
    (net (code "51") (name "PV_FUSED1") (class "Default")
      (node (ref "C66") (pin "2") (pinfunction "2_2") (pintype "passive"))
      (node (ref "C73") (pin "2") (pinfunction "2_2") (pintype "passive"))
      (node (ref "F2") (pin "2") (pinfunction "2_2") (pintype "passive"))
      (node (ref "R29") (pin "b") (pinfunction "b_b") (pintype "passive"))
    )
    (net (code "52") (name "PV_FUSED2") (class "Default")
      (node (ref "C68") (pin "2") (pinfunction "2_2") (pintype "passive"))
      (node (ref "C69") (pin "2") (pinfunction "2_2") (pintype "passive"))
      (node (ref "F3") (pin "2") (pinfunction "2_2") (pintype "passive"))
      (node (ref "R26") (pin "b") (pinfunction "b_b") (pintype "passive"))
    )
    (net (code "53") (name "unconnected-(IC8-INT-Pad3)") (class "Default")
      (node (ref "IC8") (pin "3") (pinfunction "INT_3") (pintype "power_in"))
    )
    (net (code "54") (name "unconnected-(IC9-INT-Pad3)") (class "Default")
      (node (ref "IC9") (pin "3") (pinfunction "INT_3") (pintype "power_in"))
    )
  )
)
